# CPU.net
KiCad netlist of a schematic drawn in Altium Designer
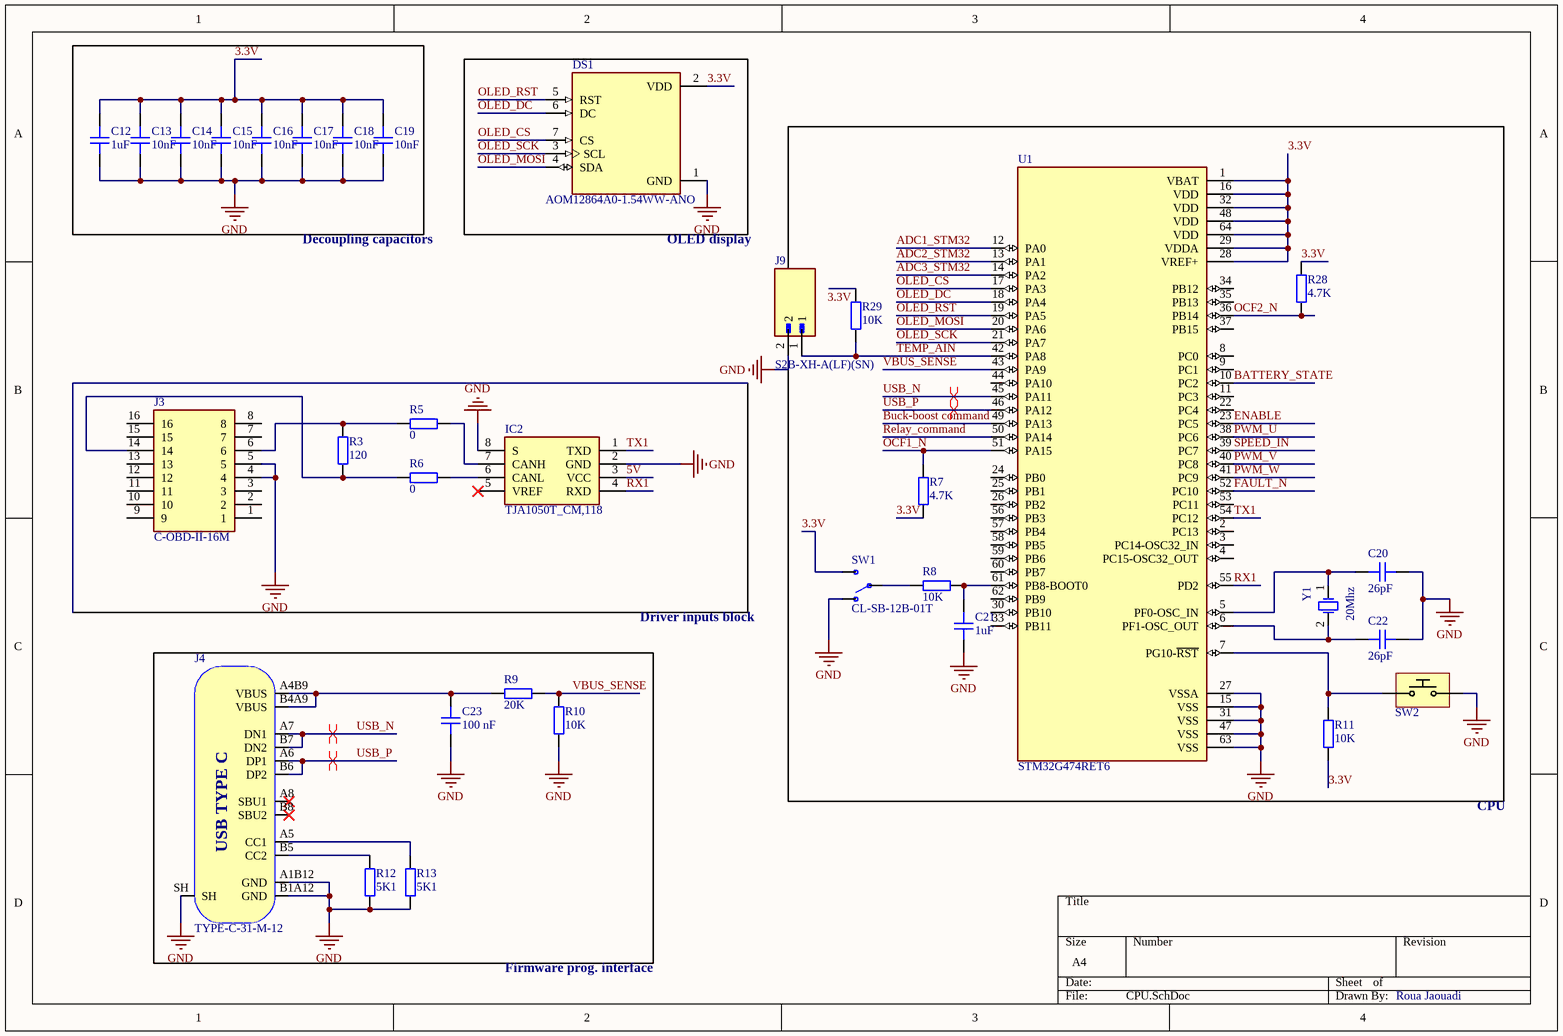
[diagram p0: CPU.SchDoc]

(export (version "E")
  (design (tool "Eeschema 10.0.6"))
  (components
    (comp (ref "C12")
      (value "1uF")
      (footprint "CAP_0603")
      (description "Capacitor SMD 0603")
      (libsource (lib "Schematic-Lib-PhilsLab") (part "CAP_0603"))
    )
    (comp (ref "C13")
      (value "10nF")
      (footprint "CAP_0603")
      (description "Capacitor SMD 0603")
      (libsource (lib "Schematic-Lib-PhilsLab") (part "CAP_0603"))
    )
    (comp (ref "C14")
      (value "10nF")
      (footprint "CAP_0603")
      (description "Capacitor SMD 0603")
      (libsource (lib "Schematic-Lib-PhilsLab") (part "CAP_0603"))
    )
    (comp (ref "C15")
      (value "10nF")
      (footprint "CAP_0603")
      (description "Capacitor SMD 0603")
      (libsource (lib "Schematic-Lib-PhilsLab") (part "CAP_0603"))
    )
    (comp (ref "C16")
      (value "10nF")
      (footprint "CAP_0603")
      (description "Capacitor SMD 0603")
      (libsource (lib "Schematic-Lib-PhilsLab") (part "CAP_0603"))
    )
    (comp (ref "C17")
      (value "10nF")
      (footprint "CAP_0603")
      (description "Capacitor SMD 0603")
      (libsource (lib "Schematic-Lib-PhilsLab") (part "CAP_0603"))
    )
    (comp (ref "C18")
      (value "10nF")
      (footprint "CAP_0603")
      (description "Capacitor SMD 0603")
      (libsource (lib "Schematic-Lib-PhilsLab") (part "CAP_0603"))
    )
    (comp (ref "C19")
      (value "10nF")
      (footprint "CAP_0603")
      (description "Capacitor SMD 0603")
      (libsource (lib "Schematic-Lib-PhilsLab") (part "CAP_0603"))
    )
    (comp (ref "C20")
      (value "26pF")
      (footprint "CAP_0603")
      (description "Capacitor SMD 0603")
      (libsource (lib "Schlib1") (part "CAP_0603"))
    )
    (comp (ref "C21")
      (value "1uF")
      (footprint "CAP_0603")
      (description "Capacitor SMD 0603")
      (libsource (lib "Schematic-Lib-PhilsLab") (part "CAP_0603"))
    )
    (comp (ref "C22")
      (value "26pF")
      (footprint "CAP_0603")
      (description "Capacitor SMD 0603")
      (libsource (lib "Schlib1") (part "CAP_0603"))
    )
    (comp (ref "C23")
      (value "100 nF")
      (footprint "Footprint-Lib-PhilsLab:CAP_0603")
      (description "Capacitor SMD 0603")
      (libsource (lib "Schematic-Lib-PhilsLab") (part "CAP_0603"))
    )
    (comp (ref "DS1")
      (value "AOM12864A0-1.54WW-ANO")
      (footprint "LCD_AOM12864A0-1.54WW-ANO:LCD_AOM12864A0-1.54WW-ANO")
      (description "Non-Touch Graphic LCD Display Module - White OLED SPI 1.54 (39.12mm) 128 x 64")
      (fields (field (name "MF") "Orient Display"))
      (libsource (lib "AOM12864A0-1.54WW-ANO") (part "AOM12864A0-1.54WW-ANO"))
    )
    (comp (ref "IC2")
      (value "TJA1050T_CM,118")
      (footprint "SamacSys:SOIC127P600X175-8N")
      (description "Integrated Circuit")
      (fields
        (field (name "MANUFACTURER_PART_NUMBER") "TJA1050T/CM,118")
        (field (name "MOUSER PART NUMBER") "771-TJA1050T/CM118")
      )
      (libsource (lib "*") (part "TJA1050T_CM,118"))
    )
    (comp (ref "J3")
      (value "C-OBD-II-16M")
      (footprint "COMTECH_C-OBD-II-16M:COMTECH_C-OBD-II-16M")
      (description "OBD II 16pin 90 Degree Angle Male Plug Connector")
      (fields (field (name "MF") "Comtech Electronic Co., LTD"))
      (libsource (lib "C-OBD-II-16M") (part "C-OBD-II-16M"))
    )
    (comp (ref "J4")
      (value "TYPE-C-31-M-12")
      (footprint "Footprint-Lib-PhilsLab:TYPE-C-31-M-12")
      (description "USB Type C Connector Horizontal SMT")
      (fields (field (name "MANUFACTURER") "Koren Hroparts"))
      (libsource (lib "Schematic-Lib-PhilsLab") (part "TYPE-C-31-M-12"))
    )
    (comp (ref "J9")
      (value "S2B-XH-A(LF)(SN)")
      (footprint "JST_S2B-XH-A(LF)(SN):JST_S2B-XH-A(LF)(SN)")
      (description "Connector Header Through Hole, Right Angle 2 position 0.098 (2.50mm)")
      (fields (field (name "MF") "JST Sales"))
      (libsource (lib "S2B-XH-A(LF)(SN)") (part "S2B-XH-A(LF)(SN)"))
    )
    (comp (ref "R3")
      (value "120")
      (footprint "RES_0603")
      (description "Resistor SMD 0603")
      (libsource (lib "Schlib1") (part "RES_0603"))
    )
    (comp (ref "R5")
      (value "0")
      (footprint "RES_0603")
      (description "Resistor SMD 0603")
      (libsource (lib "Schlib1") (part "RES_0603"))
    )
    (comp (ref "R6")
      (value "0")
      (footprint "RES_0603")
      (description "Resistor SMD 0603")
      (libsource (lib "Schlib1") (part "RES_0603"))
    )
    (comp (ref "R7")
      (value "4.7K")
      (footprint "RES_0402")
      (description "Resistor SMD 0402")
      (libsource (lib "Schlib1") (part "RES_0402"))
    )
    (comp (ref "R8")
      (value "10K")
      (footprint "RES_0402")
      (description "Resistor SMD 0402")
      (libsource (lib "Schlib1") (part "RES_0402"))
    )
    (comp (ref "R9")
      (value "20K")
      (footprint "RES_0402")
      (description "Resistor SMD 0402")
      (libsource (lib "Schlib1") (part "RES_0402"))
    )
    (comp (ref "R10")
      (value "10K")
      (footprint "RES_0402")
      (description "Resistor SMD 0402")
      (libsource (lib "Schlib1") (part "RES_0402"))
    )
    (comp (ref "R11")
      (value "10K")
      (footprint "RES_0402")
      (description "Resistor SMD 0402")
      (libsource (lib "Schlib1") (part "RES_0402"))
    )
    (comp (ref "R12")
      (value "5K1")
      (footprint "RES_0402")
      (description "Resistor SMD 0402")
      (libsource (lib "Schlib1") (part "RES_0402"))
    )
    (comp (ref "R13")
      (value "5K1")
      (footprint "RES_0402")
      (description "Resistor SMD 0402")
      (libsource (lib "Schlib1") (part "RES_0402"))
    )
    (comp (ref "R28")
      (value "4.7K")
      (footprint "RES_0402")
      (description "Resistor SMD 0402")
      (libsource (lib "Schlib1") (part "RES_0402"))
    )
    (comp (ref "R29")
      (value "10K")
      (footprint "RES_0402")
      (description "Resistor SMD 0402")
      (libsource (lib "Schlib1") (part "RES_0402"))
    )
    (comp (ref "SW1")
      (value "CL-SB-12B-01T")
      (footprint "CL-SB-12B-01T:CL-SB-12B-01T")
      (description "Slide Switch SPDT Surface Mount")
      (fields (field (name "MF") "Nidec Copal"))
      (libsource (lib "CL-SB-12B-01T") (part "CL-SB-12B-01T"))
    )
    (comp (ref "SW2")
      (value "Tactile Switch")
      (footprint "PTS815")
      (description "Tactile Switches Tact Switch, 12 VDC, 50 mA, 4.2x3.2, 2.5mm H, 180gf, J leadspp SPST")
      (fields
        (field (name "MANUFACTURER") "C&K Switches")
        (field (name "MANUFACTURER PART NUMBER") "PTS815 SJM 250 SMTR LFS")
      )
      (libsource (lib "Schlib1") (part "PTS815-SJM-250-SMTR-LFS"))
    )
    (comp (ref "U1")
      (value "STM32G474RET6")
      (footprint "QFP50P1200X1200X160-64N:QFP50P1200X1200X160-64N")
      (fields (field (name "MF") "STMicroelectronics"))
      (libsource (lib "STM32G474RET6") (part "STM32G474RET6"))
    )
    (comp (ref "Y1")
      (value "20Mhz")
      (footprint "WE-XTAL:WE-XTAL_HC49/4HSMX")
      (description "WE-XTAL Quartz Crystal, SMT, HC49/4HSMX, 3.6864 MHz, ±30ppm")
      (fields
        (field (name "MANUFACTURER PART NUMBER") "830003260")
        (field (name "MANUFACTURER") "Wurth Elektronik")
      )
      (libsource (lib "WE-XTAL") (part "830003260"))
    )
  )
  (nets
    (net (code "1") (name "/3.3V") (class "Default")
      (node (ref "C12") (pin "1") (pinfunction "1_1") (pintype "passive"))
      (node (ref "C13") (pin "1") (pinfunction "1_1") (pintype "passive"))
      (node (ref "C14") (pin "1") (pinfunction "1_1") (pintype "passive"))
      (node (ref "C15") (pin "1") (pinfunction "1_1") (pintype "passive"))
      (node (ref "C16") (pin "1") (pinfunction "1_1") (pintype "passive"))
      (node (ref "C17") (pin "1") (pinfunction "1_1") (pintype "passive"))
      (node (ref "C18") (pin "1") (pinfunction "1_1") (pintype "passive"))
      (node (ref "C19") (pin "1") (pinfunction "1_1") (pintype "passive"))
      (node (ref "DS1") (pin "2") (pinfunction "VDD_2") (pintype "power_in"))
      (node (ref "R11") (pin "2") (pinfunction "2_2") (pintype "passive"))
      (node (ref "R28") (pin "1") (pinfunction "1_1") (pintype "passive"))
      (node (ref "R29") (pin "2") (pinfunction "2_2") (pintype "passive"))
      (node (ref "R7") (pin "2") (pinfunction "2_2") (pintype "passive"))
      (node (ref "SW1") (pin "3") (pinfunction "3_3") (pintype "passive"))
      (node (ref "U1") (pin "1") (pinfunction "VBAT_1") (pintype "power_in"))
      (node (ref "U1") (pin "16") (pinfunction "VDD_16") (pintype "power_in"))
      (node (ref "U1") (pin "28") (pinfunction "VREF+_28") (pintype "power_in"))
      (node (ref "U1") (pin "29") (pinfunction "VDDA_29") (pintype "power_in"))
      (node (ref "U1") (pin "32") (pinfunction "VDD_32") (pintype "power_in"))
      (node (ref "U1") (pin "48") (pinfunction "VDD_48") (pintype "power_in"))
      (node (ref "U1") (pin "64") (pinfunction "VDD_64") (pintype "power_in"))
    )
    (net (code "2") (name "/5V") (class "Default")
      (node (ref "IC2") (pin "3") (pinfunction "VCC_3") (pintype "passive"))
    )
    (net (code "3") (name "/ADC1_STM32") (class "Default")
      (node (ref "U1") (pin "12") (pinfunction "PA0_12") (pintype "bidirectional"))
    )
    (net (code "4") (name "/ADC2_STM32") (class "Default")
      (node (ref "U1") (pin "13") (pinfunction "PA1_13") (pintype "bidirectional"))
    )
    (net (code "5") (name "/ADC3_STM32") (class "Default")
      (node (ref "U1") (pin "14") (pinfunction "PA2_14") (pintype "bidirectional"))
    )
    (net (code "6") (name "/BATTERY_STATE") (class "Default")
      (node (ref "U1") (pin "10") (pinfunction "PC2_10") (pintype "bidirectional"))
    )
    (net (code "7") (name "/Buck-boost command") (class "Default")
      (node (ref "U1") (pin "49") (pinfunction "PA13_49") (pintype "bidirectional"))
    )
    (net (code "8") (name "/ENABLE") (class "Default")
      (node (ref "U1") (pin "23") (pinfunction "PC5_23") (pintype "bidirectional"))
    )
    (net (code "9") (name "/FAULT_N") (class "Default")
      (node (ref "U1") (pin "52") (pinfunction "PC10_52") (pintype "bidirectional"))
    )
    (net (code "10") (name "/OCF1_N") (class "Default")
      (node (ref "R7") (pin "1") (pinfunction "1_1") (pintype "passive"))
      (node (ref "U1") (pin "51") (pinfunction "PA15_51") (pintype "bidirectional"))
    )
    (net (code "11") (name "/OCF2_N") (class "Default")
      (node (ref "R28") (pin "2") (pinfunction "2_2") (pintype "passive"))
      (node (ref "U1") (pin "36") (pinfunction "PB14_36") (pintype "bidirectional"))
    )
    (net (code "12") (name "/OLED_CS") (class "Default")
      (node (ref "DS1") (pin "7") (pinfunction "CS_7") (pintype "input"))
      (node (ref "U1") (pin "17") (pinfunction "PA3_17") (pintype "bidirectional"))
    )
    (net (code "13") (name "/OLED_DC") (class "Default")
      (node (ref "DS1") (pin "6") (pinfunction "DC_6") (pintype "input"))
      (node (ref "U1") (pin "18") (pinfunction "PA4_18") (pintype "bidirectional"))
    )
    (net (code "14") (name "/OLED_MOSI") (class "Default")
      (node (ref "DS1") (pin "4") (pinfunction "SDA_4") (pintype "bidirectional"))
      (node (ref "U1") (pin "20") (pinfunction "PA6_20") (pintype "bidirectional"))
    )
    (net (code "15") (name "/OLED_RST") (class "Default")
      (node (ref "DS1") (pin "5") (pinfunction "RST_5") (pintype "input"))
      (node (ref "U1") (pin "19") (pinfunction "PA5_19") (pintype "bidirectional"))
    )
    (net (code "16") (name "/OLED_SCK") (class "Default")
      (node (ref "DS1") (pin "3") (pinfunction "SCL_3") (pintype "input"))
      (node (ref "U1") (pin "21") (pinfunction "PA7_21") (pintype "bidirectional"))
    )
    (net (code "17") (name "/PWM_U") (class "Default")
      (node (ref "U1") (pin "38") (pinfunction "PC6_38") (pintype "bidirectional"))
    )
    (net (code "18") (name "/PWM_V") (class "Default")
      (node (ref "U1") (pin "40") (pinfunction "PC8_40") (pintype "bidirectional"))
    )
    (net (code "19") (name "/PWM_W") (class "Default")
      (node (ref "U1") (pin "41") (pinfunction "PC9_41") (pintype "bidirectional"))
    )
    (net (code "20") (name "/RX1") (class "Default")
      (node (ref "IC2") (pin "4") (pinfunction "RXD_4") (pintype "passive"))
      (node (ref "U1") (pin "55") (pinfunction "PD2_55") (pintype "bidirectional"))
    )
    (net (code "21") (name "/Relay_command") (class "Default")
      (node (ref "U1") (pin "50") (pinfunction "PA14_50") (pintype "bidirectional"))
    )
    (net (code "22") (name "/SPEED_IN") (class "Default")
      (node (ref "U1") (pin "39") (pinfunction "PC7_39") (pintype "bidirectional"))
    )
    (net (code "23") (name "/TEMP_AIN") (class "Default")
      (node (ref "J9") (pin "1") (pinfunction "1_1") (pintype "passive"))
      (node (ref "R29") (pin "1") (pinfunction "1_1") (pintype "passive"))
      (node (ref "U1") (pin "42") (pinfunction "PA8_42") (pintype "bidirectional"))
    )
    (net (code "24") (name "/TX1") (class "Default")
      (node (ref "IC2") (pin "1") (pinfunction "TXD_1") (pintype "passive"))
      (node (ref "U1") (pin "54") (pinfunction "PC12_54") (pintype "bidirectional"))
    )
    (net (code "25") (name "/USB_N") (class "Default")
      (node (ref "J4") (pin "A7") (pinfunction "DN1_A7") (pintype "bidirectional"))
      (node (ref "J4") (pin "B7") (pinfunction "DN2_B7") (pintype "bidirectional"))
      (node (ref "U1") (pin "45") (pinfunction "PA11_45") (pintype "bidirectional"))
    )
    (net (code "26") (name "/USB_P") (class "Default")
      (node (ref "J4") (pin "A6") (pinfunction "DP1_A6") (pintype "bidirectional"))
      (node (ref "J4") (pin "B6") (pinfunction "DP2_B6") (pintype "bidirectional"))
      (node (ref "U1") (pin "46") (pinfunction "PA12_46") (pintype "bidirectional"))
    )
    (net (code "27") (name "/VBUS_SENSE") (class "Default")
      (node (ref "R10") (pin "1") (pinfunction "1_1") (pintype "passive"))
      (node (ref "R9") (pin "2") (pinfunction "2_2") (pintype "passive"))
      (node (ref "U1") (pin "43") (pinfunction "PA9_43") (pintype "bidirectional"))
    )
    (net (code "28") (name "GND") (class "Default")
      (node (ref "C12") (pin "2") (pinfunction "2_2") (pintype "passive"))
      (node (ref "C13") (pin "2") (pinfunction "2_2") (pintype "passive"))
      (node (ref "C14") (pin "2") (pinfunction "2_2") (pintype "passive"))
      (node (ref "C15") (pin "2") (pinfunction "2_2") (pintype "passive"))
      (node (ref "C16") (pin "2") (pinfunction "2_2") (pintype "passive"))
      (node (ref "C17") (pin "2") (pinfunction "2_2") (pintype "passive"))
      (node (ref "C18") (pin "2") (pinfunction "2_2") (pintype "passive"))
      (node (ref "C19") (pin "2") (pinfunction "2_2") (pintype "passive"))
      (node (ref "C20") (pin "2") (pinfunction "2_2") (pintype "passive"))
      (node (ref "C21") (pin "2") (pinfunction "2_2") (pintype "passive"))
      (node (ref "C22") (pin "2") (pinfunction "2_2") (pintype "passive"))
      (node (ref "C23") (pin "2") (pinfunction "2_2") (pintype "passive"))
      (node (ref "DS1") (pin "1") (pinfunction "GND_1") (pintype "power_in"))
      (node (ref "IC2") (pin "2") (pinfunction "GND_2") (pintype "passive"))
      (node (ref "IC2") (pin "8") (pinfunction "S_8") (pintype "passive"))
      (node (ref "J3") (pin "4") (pinfunction "4_4") (pintype "passive"))
      (node (ref "J3") (pin "5") (pinfunction "5_5") (pintype "passive"))
      (node (ref "J4") (pin "A1B12") (pinfunction "GND_A1B12") (pintype "power_in"))
      (node (ref "J4") (pin "B1A12") (pinfunction "GND_B1A12") (pintype "power_in"))
      (node (ref "J4") (pin "SH") (pinfunction "SH_SH") (pintype "power_in"))
      (node (ref "J9") (pin "2") (pinfunction "2_2") (pintype "passive"))
      (node (ref "R10") (pin "2") (pinfunction "2_2") (pintype "passive"))
      (node (ref "R12") (pin "2") (pinfunction "2_2") (pintype "passive"))
      (node (ref "R13") (pin "2") (pinfunction "2_2") (pintype "passive"))
      (node (ref "SW1") (pin "1") (pinfunction "1_1") (pintype "passive"))
      (node (ref "SW2") (pin "2") (pinfunction "2_2") (pintype "passive"))
      (node (ref "U1") (pin "15") (pinfunction "VSS_15") (pintype "power_in"))
      (node (ref "U1") (pin "27") (pinfunction "VSSA_27") (pintype "power_in"))
      (node (ref "U1") (pin "31") (pinfunction "VSS_31") (pintype "power_in"))
      (node (ref "U1") (pin "47") (pinfunction "VSS_47") (pintype "power_in"))
      (node (ref "U1") (pin "63") (pinfunction "VSS_63") (pintype "power_in"))
    )
    (net (code "29") (name "Net-(C23-Pad1)") (class "Default")
      (node (ref "C23") (pin "1") (pinfunction "1_1") (pintype "passive"))
      (node (ref "J4") (pin "A4B9") (pinfunction "VBUS_A4B9") (pintype "power_in"))
      (node (ref "J4") (pin "B4A9") (pinfunction "VBUS_B4A9") (pintype "power_in"))
      (node (ref "R9") (pin "1") (pinfunction "1_1") (pintype "passive"))
    )
    (net (code "30") (name "Net-(IC2-CANH)") (class "Default")
      (node (ref "IC2") (pin "7") (pinfunction "CANH_7") (pintype "passive"))
      (node (ref "R5") (pin "2") (pinfunction "2_2") (pintype "passive"))
    )
    (net (code "31") (name "Net-(IC2-CANL)") (class "Default")
      (node (ref "IC2") (pin "6") (pinfunction "CANL_6") (pintype "passive"))
      (node (ref "R6") (pin "2") (pinfunction "2_2") (pintype "passive"))
    )
    (net (code "32") (name "Net-(J3-Pad6)") (class "Default")
      (node (ref "J3") (pin "6") (pinfunction "6_6") (pintype "passive"))
      (node (ref "R3") (pin "1") (pinfunction "1_1") (pintype "passive"))
      (node (ref "R5") (pin "1") (pinfunction "1_1") (pintype "passive"))
    )
    (net (code "33") (name "Net-(J3-Pad14)") (class "Default")
      (node (ref "J3") (pin "14") (pinfunction "14_14") (pintype "passive"))
      (node (ref "R3") (pin "2") (pinfunction "2_2") (pintype "passive"))
      (node (ref "R6") (pin "1") (pinfunction "1_1") (pintype "passive"))
    )
    (net (code "34") (name "Net-(J4-CC1)") (class "Default")
      (node (ref "J4") (pin "A5") (pinfunction "CC1_A5") (pintype "passive"))
      (node (ref "R13") (pin "1") (pinfunction "1_1") (pintype "passive"))
    )
    (net (code "35") (name "Net-(J4-CC2)") (class "Default")
      (node (ref "J4") (pin "B5") (pinfunction "CC2_B5") (pintype "tri_state"))
      (node (ref "R12") (pin "1") (pinfunction "1_1") (pintype "passive"))
    )
    (net (code "36") (name "Net-(R8-Pad1)") (class "Default")
      (node (ref "R8") (pin "1") (pinfunction "1_1") (pintype "passive"))
      (node (ref "SW1") (pin "C") (pinfunction "C_C") (pintype "passive"))
    )
    (net (code "37") (name "Net-(U1-PB8-BOOT0)") (class "Default")
      (node (ref "C21") (pin "1") (pinfunction "1_1") (pintype "passive"))
      (node (ref "R8") (pin "2") (pinfunction "2_2") (pintype "passive"))
      (node (ref "U1") (pin "61") (pinfunction "PB8-BOOT0_61") (pintype "bidirectional"))
    )
    (net (code "38") (name "Net-(U1-PF0-OSC_IN)") (class "Default")
      (node (ref "C20") (pin "1") (pinfunction "1_1") (pintype "passive"))
      (node (ref "U1") (pin "5") (pinfunction "PF0-OSC_IN_5") (pintype "bidirectional"))
      (node (ref "Y1") (pin "1") (pinfunction "OSC1_1") (pintype "passive"))
    )
    (net (code "39") (name "Net-(U1-PF1-OSC_OUT)") (class "Default")
      (node (ref "C22") (pin "1") (pinfunction "1_1") (pintype "passive"))
      (node (ref "U1") (pin "6") (pinfunction "PF1-OSC_OUT_6") (pintype "bidirectional"))
      (node (ref "Y1") (pin "2") (pinfunction "OSC2_2") (pintype "passive"))
    )
    (net (code "40") (name "Net-(U1-PG10-~{RST})") (class "Default")
      (node (ref "R11") (pin "1") (pinfunction "1_1") (pintype "passive"))
      (node (ref "SW2") (pin "1") (pinfunction "1_1") (pintype "passive"))
      (node (ref "U1") (pin "7") (pinfunction "PG10-~{RST}_7") (pintype "bidirectional"))
    )
    (net (code "41") (name "unconnected-(IC2-VREF-Pad5)") (class "Default")
      (node (ref "IC2") (pin "5") (pinfunction "VREF_5") (pintype "passive+no_connect"))
    )
    (net (code "42") (name "unconnected-(J3-Pad1)") (class "Default")
      (node (ref "J3") (pin "1") (pinfunction "1_1") (pintype "passive"))
    )
    (net (code "43") (name "unconnected-(J3-Pad2)") (class "Default")
      (node (ref "J3") (pin "2") (pinfunction "2_2") (pintype "passive"))
    )
    (net (code "44") (name "unconnected-(J3-Pad3)") (class "Default")
      (node (ref "J3") (pin "3") (pinfunction "3_3") (pintype "passive"))
    )
    (net (code "45") (name "unconnected-(J3-Pad7)") (class "Default")
      (node (ref "J3") (pin "7") (pinfunction "7_7") (pintype "passive"))
    )
    (net (code "46") (name "unconnected-(J3-Pad8)") (class "Default")
      (node (ref "J3") (pin "8") (pinfunction "8_8") (pintype "passive"))
    )
    (net (code "47") (name "unconnected-(J3-Pad9)") (class "Default")
      (node (ref "J3") (pin "9") (pinfunction "9_9") (pintype "passive"))
    )
    (net (code "48") (name "unconnected-(J3-Pad10)") (class "Default")
      (node (ref "J3") (pin "10") (pinfunction "10_10") (pintype "passive"))
    )
    (net (code "49") (name "unconnected-(J3-Pad11)") (class "Default")
      (node (ref "J3") (pin "11") (pinfunction "11_11") (pintype "passive"))
    )
    (net (code "50") (name "unconnected-(J3-Pad12)") (class "Default")
      (node (ref "J3") (pin "12") (pinfunction "12_12") (pintype "passive"))
    )
    (net (code "51") (name "unconnected-(J3-Pad13)") (class "Default")
      (node (ref "J3") (pin "13") (pinfunction "13_13") (pintype "passive"))
    )
    (net (code "52") (name "unconnected-(J3-Pad15)") (class "Default")
      (node (ref "J3") (pin "15") (pinfunction "15_15") (pintype "passive"))
    )
    (net (code "53") (name "unconnected-(J3-Pad16)") (class "Default")
      (node (ref "J3") (pin "16") (pinfunction "16_16") (pintype "passive"))
    )
    (net (code "54") (name "unconnected-(J4-SBU1-PadA8)") (class "Default")
      (node (ref "J4") (pin "A8") (pinfunction "SBU1_A8") (pintype "bidirectional+no_connect"))
    )
    (net (code "55") (name "unconnected-(J4-SBU2-PadB8)") (class "Default")
      (node (ref "J4") (pin "B8") (pinfunction "SBU2_B8") (pintype "bidirectional+no_connect"))
    )
    (net (code "56") (name "unconnected-(U1-PA10-Pad44)") (class "Default")
      (node (ref "U1") (pin "44") (pinfunction "PA10_44") (pintype "bidirectional"))
    )
    (net (code "57") (name "unconnected-(U1-PB0-Pad24)") (class "Default")
      (node (ref "U1") (pin "24") (pinfunction "PB0_24") (pintype "bidirectional"))
    )
    (net (code "58") (name "unconnected-(U1-PB1-Pad25)") (class "Default")
      (node (ref "U1") (pin "25") (pinfunction "PB1_25") (pintype "bidirectional"))
    )
    (net (code "59") (name "unconnected-(U1-PB2-Pad26)") (class "Default")
      (node (ref "U1") (pin "26") (pinfunction "PB2_26") (pintype "bidirectional"))
    )
    (net (code "60") (name "unconnected-(U1-PB3-Pad56)") (class "Default")
      (node (ref "U1") (pin "56") (pinfunction "PB3_56") (pintype "bidirectional"))
    )
    (net (code "61") (name "unconnected-(U1-PB4-Pad57)") (class "Default")
      (node (ref "U1") (pin "57") (pinfunction "PB4_57") (pintype "bidirectional"))
    )
    (net (code "62") (name "unconnected-(U1-PB5-Pad58)") (class "Default")
      (node (ref "U1") (pin "58") (pinfunction "PB5_58") (pintype "bidirectional"))
    )
    (net (code "63") (name "unconnected-(U1-PB6-Pad59)") (class "Default")
      (node (ref "U1") (pin "59") (pinfunction "PB6_59") (pintype "bidirectional"))
    )
    (net (code "64") (name "unconnected-(U1-PB7-Pad60)") (class "Default")
      (node (ref "U1") (pin "60") (pinfunction "PB7_60") (pintype "bidirectional"))
    )
    (net (code "65") (name "unconnected-(U1-PB9-Pad62)") (class "Default")
      (node (ref "U1") (pin "62") (pinfunction "PB9_62") (pintype "bidirectional"))
    )
    (net (code "66") (name "unconnected-(U1-PB10-Pad30)") (class "Default")
      (node (ref "U1") (pin "30") (pinfunction "PB10_30") (pintype "bidirectional"))
    )
    (net (code "67") (name "unconnected-(U1-PB11-Pad33)") (class "Default")
      (node (ref "U1") (pin "33") (pinfunction "PB11_33") (pintype "bidirectional"))
    )
    (net (code "68") (name "unconnected-(U1-PB12-Pad34)") (class "Default")
      (node (ref "U1") (pin "34") (pinfunction "PB12_34") (pintype "bidirectional"))
    )
    (net (code "69") (name "unconnected-(U1-PB13-Pad35)") (class "Default")
      (node (ref "U1") (pin "35") (pinfunction "PB13_35") (pintype "bidirectional"))
    )
    (net (code "70") (name "unconnected-(U1-PB15-Pad37)") (class "Default")
      (node (ref "U1") (pin "37") (pinfunction "PB15_37") (pintype "bidirectional"))
    )
    (net (code "71") (name "unconnected-(U1-PC0-Pad8)") (class "Default")
      (node (ref "U1") (pin "8") (pinfunction "PC0_8") (pintype "bidirectional"))
    )
    (net (code "72") (name "unconnected-(U1-PC1-Pad9)") (class "Default")
      (node (ref "U1") (pin "9") (pinfunction "PC1_9") (pintype "bidirectional"))
    )
    (net (code "73") (name "unconnected-(U1-PC3-Pad11)") (class "Default")
      (node (ref "U1") (pin "11") (pinfunction "PC3_11") (pintype "bidirectional"))
    )
    (net (code "74") (name "unconnected-(U1-PC4-Pad22)") (class "Default")
      (node (ref "U1") (pin "22") (pinfunction "PC4_22") (pintype "bidirectional"))
    )
    (net (code "75") (name "unconnected-(U1-PC11-Pad53)") (class "Default")
      (node (ref "U1") (pin "53") (pinfunction "PC11_53") (pintype "bidirectional"))
    )
    (net (code "76") (name "unconnected-(U1-PC13-Pad2)") (class "Default")
      (node (ref "U1") (pin "2") (pinfunction "PC13_2") (pintype "bidirectional"))
    )
    (net (code "77") (name "unconnected-(U1-PC14-OSC32_IN-Pad3)") (class "Default")
      (node (ref "U1") (pin "3") (pinfunction "PC14-OSC32_IN_3") (pintype "bidirectional"))
    )
    (net (code "78") (name "unconnected-(U1-PC15-OSC32_OUT-Pad4)") (class "Default")
      (node (ref "U1") (pin "4") (pinfunction "PC15-OSC32_OUT_4") (pintype "bidirectional"))
    )
  )
)
